# LoRa_Node_1_3.net
KiCad netlist of a schematic drawn in EAGLE
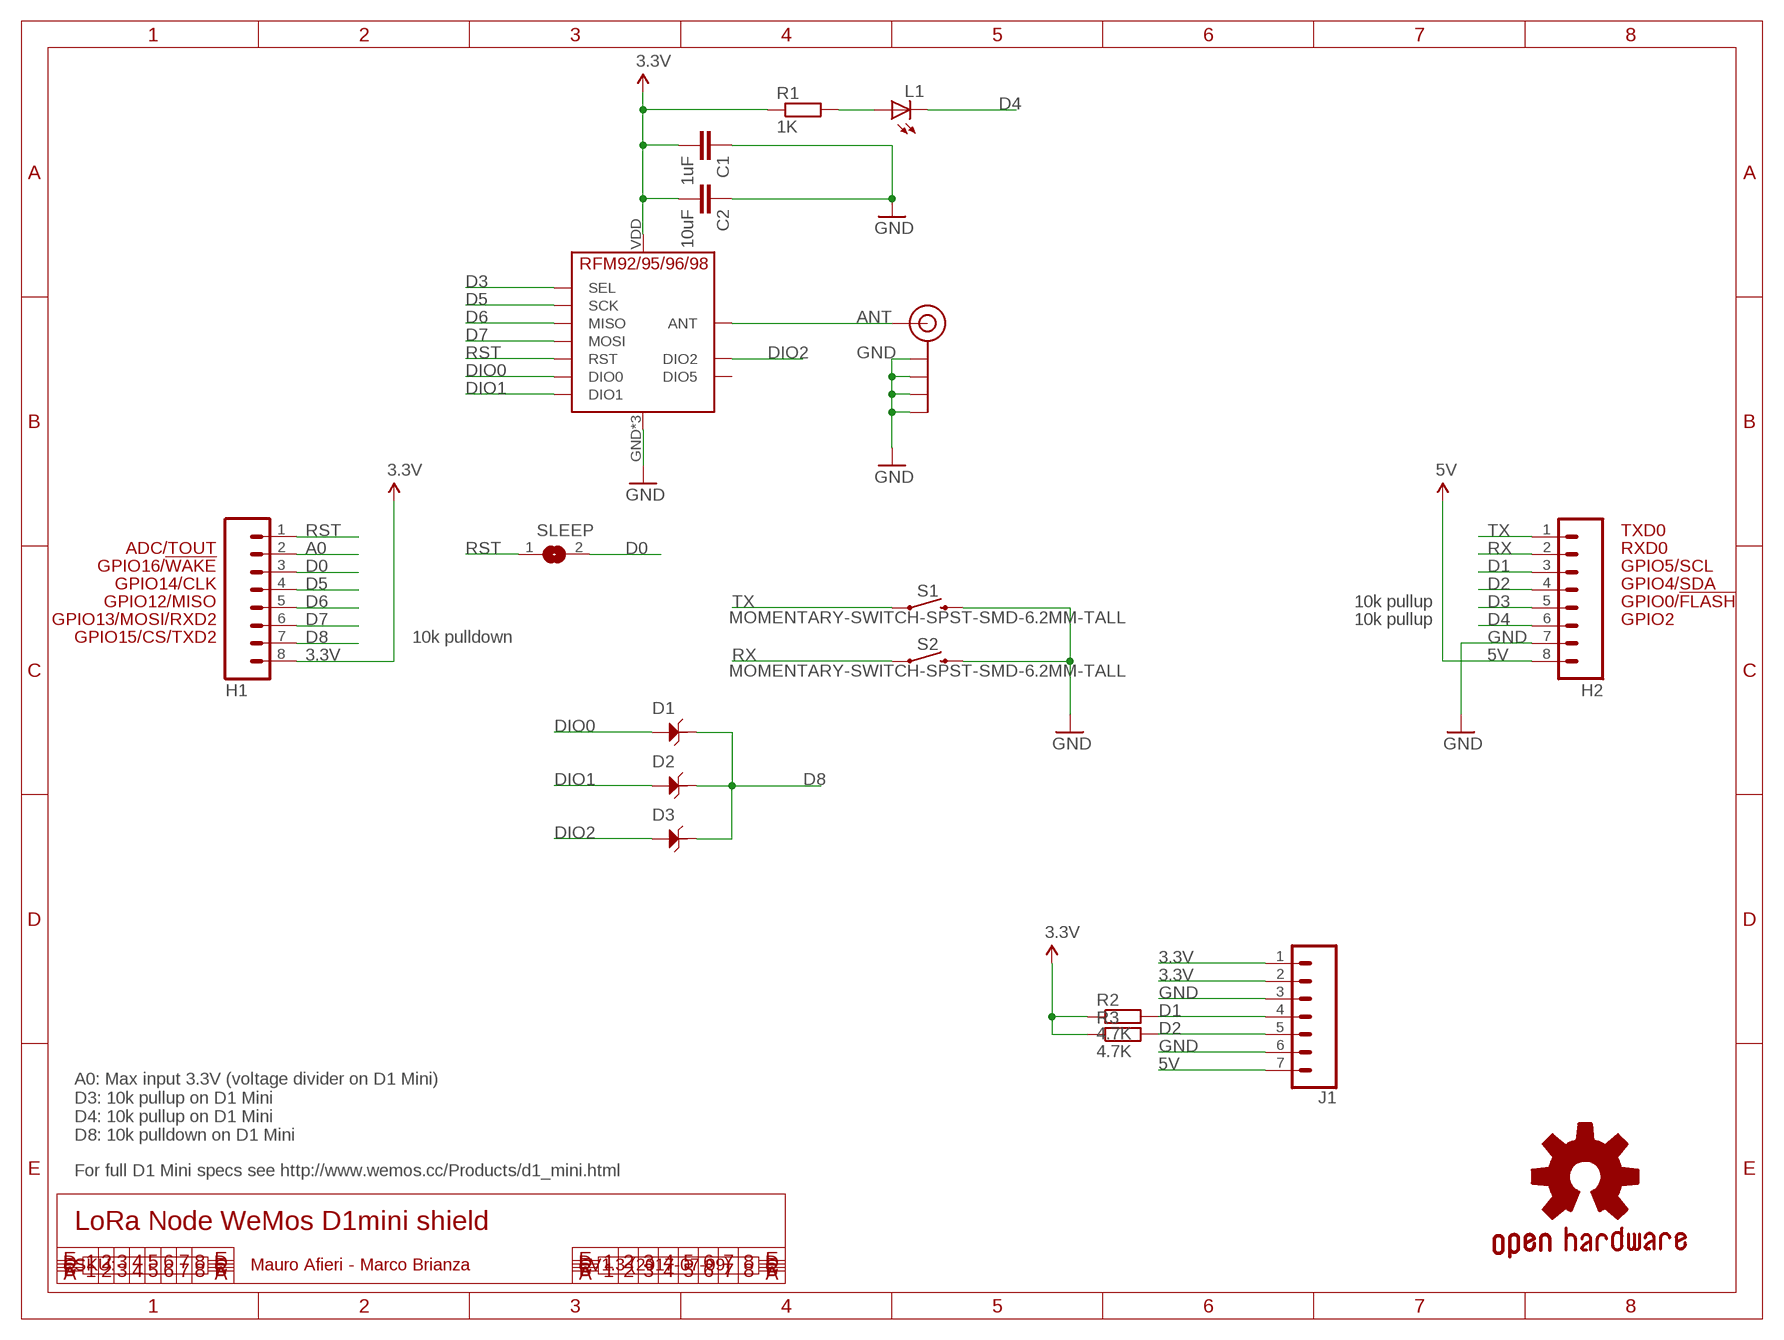
[diagram p0: schematic, sheet 1]

(export (version "E")
  (design (tool "Eeschema 10.0.6"))
  (components
    (comp (ref "C1")
      (value "1uF")
      (footprint "eagle-import:0805-CAP-LARGEPADS")
      (libsource (lib "eagle-import") (part "CAP0805-CAP-LARGEPADS"))
    )
    (comp (ref "C2")
      (value "10uF")
      (footprint "eagle-import:0805-CAP-LARGEPADS")
      (libsource (lib "eagle-import") (part "CAP0805-CAP-LARGEPADS"))
    )
    (comp (ref "D1")
      (value "D-ESD-2P-CESD5V0D1")
      (footprint "eagle-import:SOD123-2.7X1.6")
      (libsource (lib "eagle-import") (part "D-ESD-2P-CESD5V0D1"))
    )
    (comp (ref "D2")
      (value "D-ESD-2P-CESD5V0D1")
      (footprint "eagle-import:SOD123-2.7X1.6")
      (libsource (lib "eagle-import") (part "D-ESD-2P-CESD5V0D1"))
    )
    (comp (ref "D3")
      (value "D-ESD-2P-CESD5V0D1")
      (footprint "eagle-import:SOD123-2.7X1.6")
      (libsource (lib "eagle-import") (part "D-ESD-2P-CESD5V0D1"))
    )
    (comp (ref "GOLD_ORB_SM1")
      (value "OSHWLOGO_GOLD_ORB_SM")
      (footprint "eagle-import:OSHW2")
      (libsource (lib "eagle-import") (part "OSHWLOGO_GOLD_ORB_SM"))
    )
    (comp (ref "H1")
      (value "M08")
      (footprint "eagle-import:1X08")
      (libsource (lib "eagle-import") (part "M08"))
    )
    (comp (ref "H2")
      (value "M08")
      (footprint "eagle-import:1X08")
      (libsource (lib "eagle-import") (part "M08"))
    )
    (comp (ref "J$1")
      (value "ANTENNATINY")
      (footprint "eagle-import:SMA_UFL_PAD_TINY")
      (libsource (lib "eagle-import") (part "ANTENNATINY"))
    )
    (comp (ref "J1")
      (value "CONN_07")
      (footprint "eagle-import:1X07")
      (libsource (lib "eagle-import") (part "CONN_07"))
    )
    (comp (ref "L1")
      (value "LEDCHIPLED_0805")
      (footprint "eagle-import:CHIPLED_0805")
      (libsource (lib "eagle-import") (part "LEDCHIPLED_0805"))
    )
    (comp (ref "R1")
      (value "1K")
      (footprint "eagle-import:M0805")
      (libsource (lib "eagle-import") (part "R-EU_M0805"))
    )
    (comp (ref "R2")
      (value "4.7K")
      (footprint "eagle-import:M0805")
      (libsource (lib "eagle-import") (part "R-EU_M0805"))
    )
    (comp (ref "R3")
      (value "4.7K")
      (footprint "eagle-import:M0805")
      (libsource (lib "eagle-import") (part "R-EU_M0805"))
    )
    (comp (ref "S1")
      (value "MOMENTARY-SWITCH-SPST-SMD-6.2MM-TALL")
      (footprint "eagle-import:TACTILE_SWITCH_SMD_6.2MM_TALL")
      (libsource (lib "eagle-import") (part "MOMENTARY-SWITCH-SPST-SMD-6.2MM-TALL"))
    )
    (comp (ref "S2")
      (value "MOMENTARY-SWITCH-SPST-SMD-6.2MM-TALL")
      (footprint "eagle-import:TACTILE_SWITCH_SMD_6.2MM_TALL")
      (libsource (lib "eagle-import") (part "MOMENTARY-SWITCH-SPST-SMD-6.2MM-TALL"))
    )
    (comp (ref "SLEEP")
      (value "SJ")
      (footprint "eagle-import:SJ")
      (libsource (lib "eagle-import") (part "SJ"))
    )
    (comp (ref "U$2")
      (value "RFM95")
      (footprint "eagle-import:RFM95")
      (libsource (lib "eagle-import") (part "RFM95"))
    )
  )
  (nets
    (net (code "1") (name "/A0") (class "Default")
      (node (ref "H1") (pin "2") (pinfunction "2_2") (pintype "passive"))
    )
    (net (code "2") (name "/ANT") (class "Default")
      (node (ref "J$1") (pin "ANT1") (pinfunction "SIGNAL_ANT1") (pintype "bidirectional"))
      (node (ref "J$1") (pin "ANT2") (pinfunction "SIGNAL_ANT2") (pintype "bidirectional"))
      (node (ref "J$1") (pin "ANT3") (pinfunction "SIGNAL_ANT3") (pintype "bidirectional"))
      (node (ref "U$2") (pin "ANT") (pinfunction "ANT_ANT") (pintype "passive"))
    )
    (net (code "3") (name "/D0") (class "Default")
      (node (ref "H1") (pin "3") (pinfunction "3_3") (pintype "passive"))
      (node (ref "SLEEP") (pin "2") (pinfunction "2_2") (pintype "passive"))
    )
    (net (code "4") (name "/D1") (class "Default")
      (node (ref "H2") (pin "3") (pinfunction "3_3") (pintype "passive"))
      (node (ref "J1") (pin "4") (pinfunction "4_4") (pintype "passive"))
      (node (ref "R2") (pin "2") (pinfunction "2_2") (pintype "passive"))
    )
    (net (code "5") (name "/D2") (class "Default")
      (node (ref "H2") (pin "4") (pinfunction "4_4") (pintype "passive"))
      (node (ref "J1") (pin "5") (pinfunction "5_5") (pintype "passive"))
      (node (ref "R3") (pin "2") (pinfunction "2_2") (pintype "passive"))
    )
    (net (code "6") (name "/D3") (class "Default")
      (node (ref "H2") (pin "5") (pinfunction "5_5") (pintype "passive"))
      (node (ref "U$2") (pin "NSS") (pinfunction "SEL_NSS") (pintype "input"))
    )
    (net (code "7") (name "/D4") (class "Default")
      (node (ref "H2") (pin "6") (pinfunction "6_6") (pintype "passive"))
      (node (ref "L1") (pin "C") (pinfunction "C_C") (pintype "passive"))
    )
    (net (code "8") (name "/D5") (class "Default")
      (node (ref "H1") (pin "4") (pinfunction "4_4") (pintype "passive"))
      (node (ref "U$2") (pin "SCK") (pinfunction "SCK_SCK") (pintype "input"))
    )
    (net (code "9") (name "/D6") (class "Default")
      (node (ref "H1") (pin "5") (pinfunction "5_5") (pintype "passive"))
      (node (ref "U$2") (pin "MISO") (pinfunction "MISO_MISO") (pintype "input"))
    )
    (net (code "10") (name "/D7") (class "Default")
      (node (ref "H1") (pin "6") (pinfunction "6_6") (pintype "passive"))
      (node (ref "U$2") (pin "MOSI") (pinfunction "MOSI_MOSI") (pintype "output"))
    )
    (net (code "11") (name "/D8") (class "Default")
      (node (ref "D1") (pin "2") (pinfunction "2_2") (pintype "bidirectional"))
      (node (ref "D2") (pin "2") (pinfunction "2_2") (pintype "bidirectional"))
      (node (ref "D3") (pin "2") (pinfunction "2_2") (pintype "bidirectional"))
      (node (ref "H1") (pin "7") (pinfunction "7_7") (pintype "passive"))
    )
    (net (code "12") (name "/DIO0") (class "Default")
      (node (ref "D1") (pin "1") (pinfunction "1_1") (pintype "bidirectional"))
      (node (ref "U$2") (pin "DIO0") (pinfunction "DIO0_DIO0") (pintype "open_collector"))
    )
    (net (code "13") (name "/DIO1") (class "Default")
      (node (ref "D2") (pin "1") (pinfunction "1_1") (pintype "bidirectional"))
      (node (ref "U$2") (pin "DIO1") (pinfunction "DIO1_DIO1") (pintype "open_collector"))
    )
    (net (code "14") (name "/DIO2") (class "Default")
      (node (ref "D3") (pin "1") (pinfunction "1_1") (pintype "bidirectional"))
      (node (ref "U$2") (pin "DIO2") (pinfunction "DIO2_DIO2") (pintype "open_collector"))
    )
    (net (code "15") (name "/RST") (class "Default")
      (node (ref "H1") (pin "1") (pinfunction "1_1") (pintype "passive"))
      (node (ref "SLEEP") (pin "1") (pinfunction "1_1") (pintype "passive"))
      (node (ref "U$2") (pin "RST") (pinfunction "RST_RST") (pintype "open_collector"))
    )
    (net (code "16") (name "/RX") (class "Default")
      (node (ref "H2") (pin "2") (pinfunction "2_2") (pintype "passive"))
      (node (ref "S2") (pin "A2") (pinfunction "1_A2") (pintype "passive"))
    )
    (net (code "17") (name "/TX") (class "Default")
      (node (ref "H2") (pin "1") (pinfunction "1_1") (pintype "passive"))
      (node (ref "S1") (pin "A2") (pinfunction "1_A2") (pintype "passive"))
    )
    (net (code "18") (name "3.3V") (class "Default")
      (node (ref "C1") (pin "2") (pinfunction "2_2") (pintype "passive"))
      (node (ref "C2") (pin "2") (pinfunction "2_2") (pintype "passive"))
      (node (ref "H1") (pin "8") (pinfunction "8_8") (pintype "passive"))
      (node (ref "J1") (pin "1") (pinfunction "1_1") (pintype "passive"))
      (node (ref "J1") (pin "2") (pinfunction "2_2") (pintype "passive"))
      (node (ref "R1") (pin "1") (pinfunction "1_1") (pintype "passive"))
      (node (ref "R2") (pin "1") (pinfunction "1_1") (pintype "passive"))
      (node (ref "R3") (pin "1") (pinfunction "1_1") (pintype "passive"))
      (node (ref "U$2") (pin "VDD") (pinfunction "VCC_VDD") (pintype "power_in"))
    )
    (net (code "19") (name "5V") (class "Default")
      (node (ref "H2") (pin "8") (pinfunction "8_8") (pintype "passive"))
      (node (ref "J1") (pin "7") (pinfunction "7_7") (pintype "passive"))
    )
    (net (code "20") (name "GND") (class "Default")
      (node (ref "C1") (pin "1") (pinfunction "1_1") (pintype "passive"))
      (node (ref "C2") (pin "1") (pinfunction "1_1") (pintype "passive"))
      (node (ref "H2") (pin "7") (pinfunction "7_7") (pintype "passive"))
      (node (ref "J$1") (pin "GND1") (pinfunction "GND_GND1") (pintype "bidirectional"))
      (node (ref "J$1") (pin "GND2") (pinfunction "GND_GND2") (pintype "bidirectional"))
      (node (ref "J$1") (pin "GND3") (pinfunction "GND_GND3") (pintype "bidirectional"))
      (node (ref "J$1") (pin "GND4") (pinfunction "GND_GND4") (pintype "bidirectional"))
      (node (ref "J1") (pin "3") (pinfunction "3_3") (pintype "passive"))
      (node (ref "J1") (pin "6") (pinfunction "6_6") (pintype "passive"))
      (node (ref "S1") (pin "B2") (pinfunction "2_B2") (pintype "passive"))
      (node (ref "S2") (pin "B2") (pinfunction "2_B2") (pintype "passive"))
      (node (ref "U$2") (pin "GND") (pinfunction "GND_GND") (pintype "power_in"))
      (node (ref "U$2") (pin "GND1") (pinfunction "GND_GND1") (pintype "power_in"))
      (node (ref "U$2") (pin "GND2") (pinfunction "GND_GND2") (pintype "power_in"))
    )
    (net (code "21") (name "Net-(L1-PadA)") (class "Default")
      (node (ref "L1") (pin "A") (pinfunction "A_A") (pintype "passive"))
      (node (ref "R1") (pin "2") (pinfunction "2_2") (pintype "passive"))
    )
    (net (code "22") (name "unconnected-(U$2-PadDIO5)") (class "Default")
      (node (ref "U$2") (pin "DIO5") (pinfunction "DIO5_DIO5") (pintype "open_collector"))
    )
  )
)
